# G228X.net
KiCad netlist of a schematic drawn in EAGLE
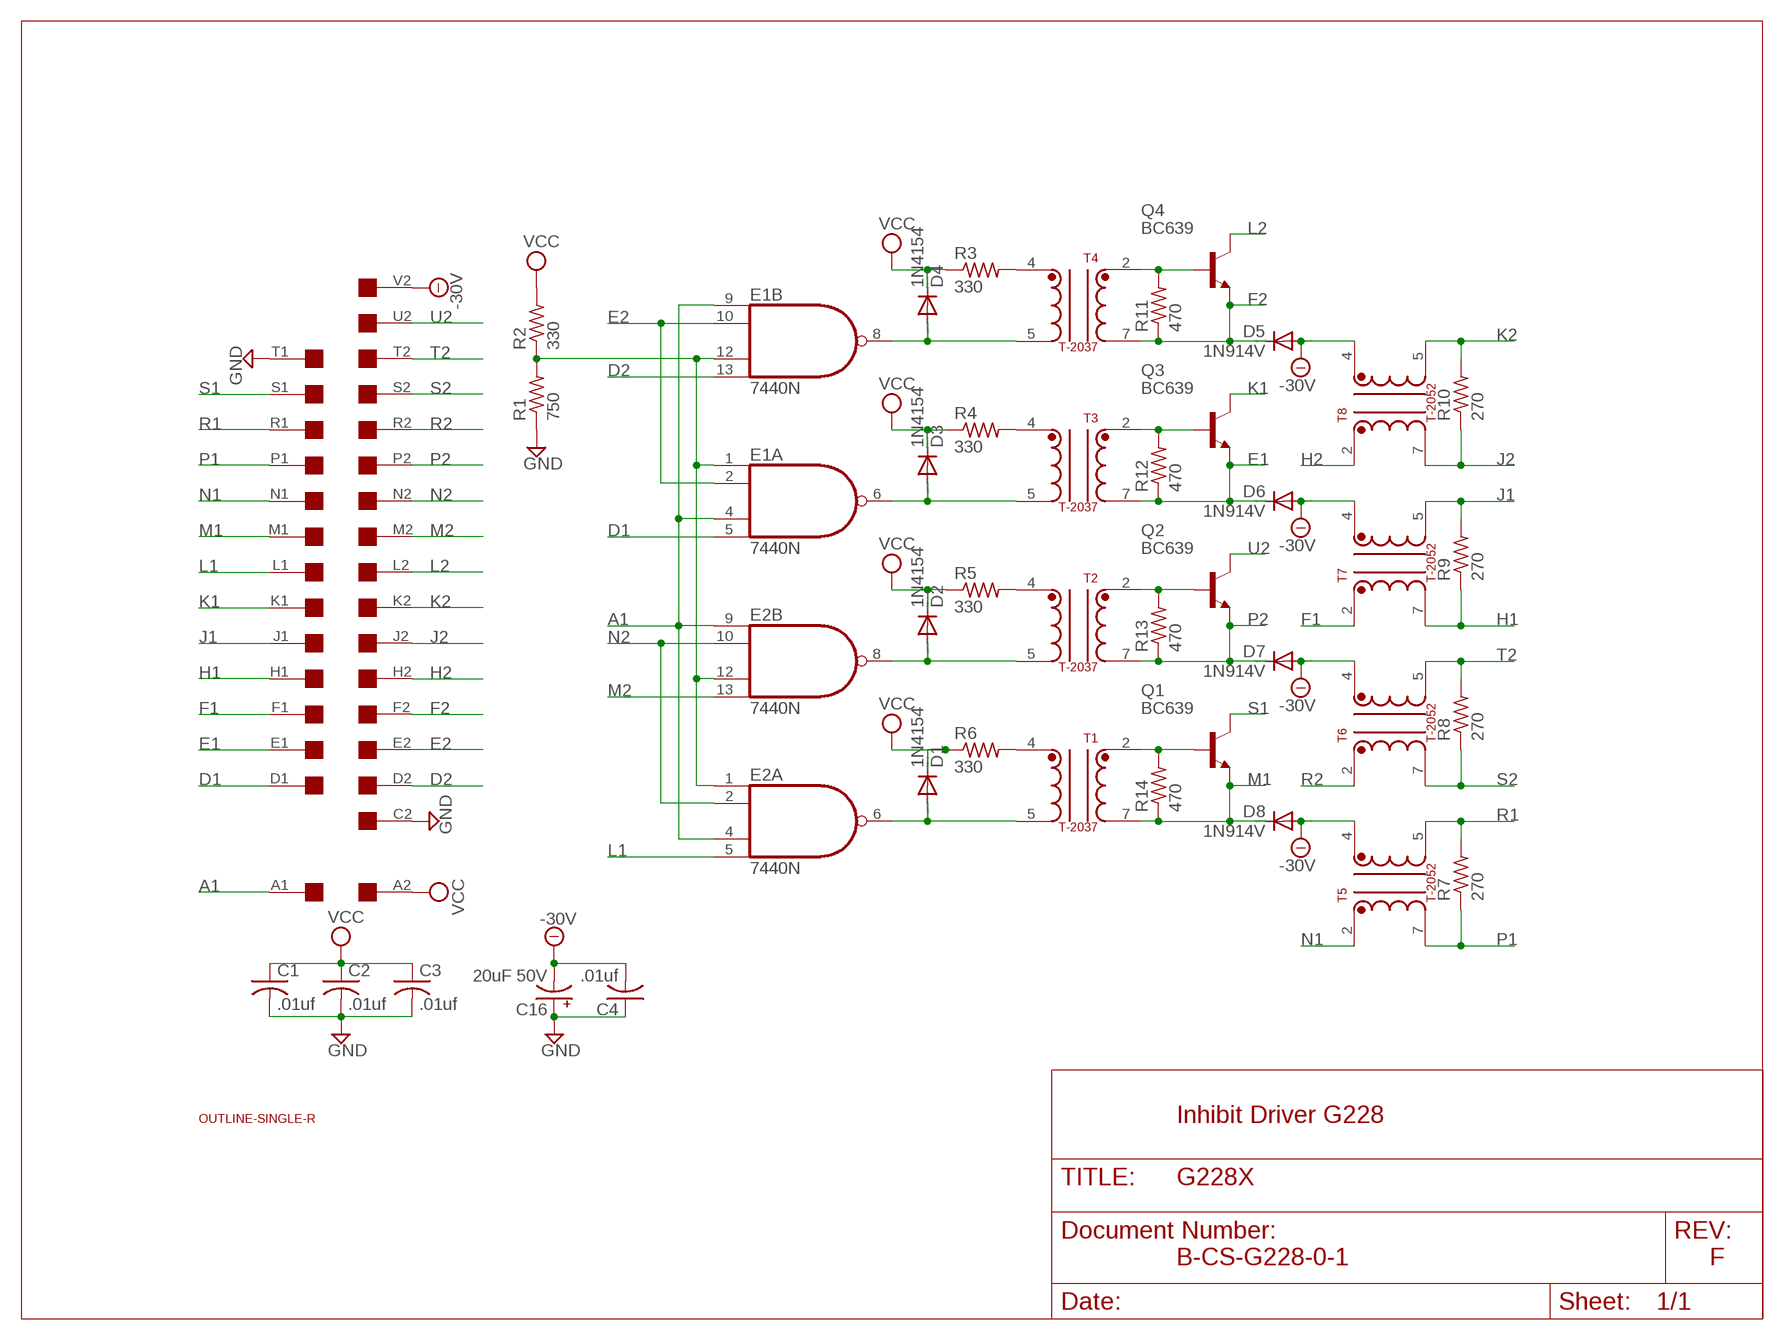
[diagram p0: schematic, sheet 1]

(export (version "E")
  (design (tool "Eeschema 10.0.6"))
  (components
    (comp (ref "C1")
      (value ".01uf")
      (footprint "eagle-import:C050-025X075")
      (libsource (lib "eagle-import") (part "C-US050-025X075"))
    )
    (comp (ref "C2")
      (value ".01uf")
      (footprint "eagle-import:C050-025X075")
      (libsource (lib "eagle-import") (part "C-US050-025X075"))
    )
    (comp (ref "C3")
      (value ".01uf")
      (footprint "eagle-import:C050-025X075")
      (libsource (lib "eagle-import") (part "C-US050-025X075"))
    )
    (comp (ref "C4")
      (value ".01uf")
      (footprint "eagle-import:C050-025X075")
      (libsource (lib "eagle-import") (part "C-US050-025X075"))
    )
    (comp (ref "C16")
      (value "20uF 50V")
      (footprint "eagle-import:E28-8")
      (libsource (lib "eagle-import") (part "CPOL-USE28-8AXIAL"))
    )
    (comp (ref "D1")
      (value "1N4154")
      (footprint "eagle-import:DO35-10")
      (libsource (lib "eagle-import") (part "1N4148DO35-10"))
    )
    (comp (ref "D2")
      (value "1N4154")
      (footprint "eagle-import:DO35-10")
      (libsource (lib "eagle-import") (part "1N4148DO35-10"))
    )
    (comp (ref "D3")
      (value "1N4154")
      (footprint "eagle-import:DO35-10")
      (libsource (lib "eagle-import") (part "1N4148DO35-10"))
    )
    (comp (ref "D4")
      (value "1N4154")
      (footprint "eagle-import:DO35-10")
      (libsource (lib "eagle-import") (part "1N4148DO35-10"))
    )
    (comp (ref "D5")
      (value "1N914V")
      (footprint "eagle-import:DO35-10")
      (libsource (lib "eagle-import") (part "1N4148DO35-10"))
    )
    (comp (ref "D6")
      (value "1N914V")
      (footprint "eagle-import:DO35-10")
      (libsource (lib "eagle-import") (part "1N4148DO35-10"))
    )
    (comp (ref "D7")
      (value "1N914V")
      (footprint "eagle-import:DO35-10")
      (libsource (lib "eagle-import") (part "1N4148DO35-10"))
    )
    (comp (ref "D8")
      (value "1N914V")
      (footprint "eagle-import:DO35-10")
      (libsource (lib "eagle-import") (part "1N4148DO35-10"))
    )
    (comp (ref "E1")
      (value "7440N")
      (footprint "eagle-import:DIL14")
      (libsource (lib "eagle-import") (part "7420NS"))
    )
    (comp (ref "E2")
      (value "7440N")
      (footprint "eagle-import:DIL14")
      (libsource (lib "eagle-import") (part "7420NS"))
    )
    (comp (ref "Q1")
      (value "BC639")
      (footprint "eagle-import:TO39")
      (libsource (lib "eagle-import") (part "-NPN-TO39-EBC2N1613"))
    )
    (comp (ref "Q2")
      (value "BC639")
      (footprint "eagle-import:TO39")
      (libsource (lib "eagle-import") (part "-NPN-TO39-EBC2N1613"))
    )
    (comp (ref "Q3")
      (value "BC639")
      (footprint "eagle-import:TO39")
      (libsource (lib "eagle-import") (part "-NPN-TO39-EBC2N1613"))
    )
    (comp (ref "Q4")
      (value "BC639")
      (footprint "eagle-import:TO39")
      (libsource (lib "eagle-import") (part "-NPN-TO39-EBC2N1613"))
    )
    (comp (ref "R1")
      (value "750")
      (footprint "eagle-import:0207_10")
      (libsource (lib "eagle-import") (part "R-US_0207/10"))
    )
    (comp (ref "R2")
      (value "330")
      (footprint "eagle-import:0207_10")
      (libsource (lib "eagle-import") (part "R-US_0207/10"))
    )
    (comp (ref "R3")
      (value "330")
      (footprint "eagle-import:0207_10")
      (libsource (lib "eagle-import") (part "R-US_0207/10"))
    )
    (comp (ref "R4")
      (value "330")
      (footprint "eagle-import:0207_10")
      (libsource (lib "eagle-import") (part "R-US_0207/10"))
    )
    (comp (ref "R5")
      (value "330")
      (footprint "eagle-import:0207_10")
      (libsource (lib "eagle-import") (part "R-US_0207/10"))
    )
    (comp (ref "R6")
      (value "330")
      (footprint "eagle-import:0207_10")
      (libsource (lib "eagle-import") (part "R-US_0207/10"))
    )
    (comp (ref "R7")
      (value "270")
      (footprint "eagle-import:0207_10")
      (libsource (lib "eagle-import") (part "R-US_0207/10"))
    )
    (comp (ref "R8")
      (value "270")
      (footprint "eagle-import:0207_10")
      (libsource (lib "eagle-import") (part "R-US_0207/10"))
    )
    (comp (ref "R9")
      (value "270")
      (footprint "eagle-import:0207_10")
      (libsource (lib "eagle-import") (part "R-US_0207/10"))
    )
    (comp (ref "R10")
      (value "270")
      (footprint "eagle-import:0207_10")
      (libsource (lib "eagle-import") (part "R-US_0207/10"))
    )
    (comp (ref "R11")
      (value "470")
      (footprint "eagle-import:0207_10")
      (libsource (lib "eagle-import") (part "R-US_0207/10"))
    )
    (comp (ref "R12")
      (value "470")
      (footprint "eagle-import:0207_10")
      (libsource (lib "eagle-import") (part "R-US_0207/10"))
    )
    (comp (ref "R13")
      (value "470")
      (footprint "eagle-import:0207_10")
      (libsource (lib "eagle-import") (part "R-US_0207/10"))
    )
    (comp (ref "R14")
      (value "470")
      (footprint "eagle-import:0207_10")
      (libsource (lib "eagle-import") (part "R-US_0207/10"))
    )
    (comp (ref "T1")
      (value "T-2037")
      (footprint "eagle-import:TRANSFORMER")
      (libsource (lib "eagle-import") (part "T-2037"))
    )
    (comp (ref "T2")
      (value "T-2037")
      (footprint "eagle-import:TRANSFORMER")
      (libsource (lib "eagle-import") (part "T-2037"))
    )
    (comp (ref "T3")
      (value "T-2037")
      (footprint "eagle-import:TRANSFORMER")
      (libsource (lib "eagle-import") (part "T-2037"))
    )
    (comp (ref "T4")
      (value "T-2037")
      (footprint "eagle-import:TRANSFORMER")
      (libsource (lib "eagle-import") (part "T-2037"))
    )
    (comp (ref "T5")
      (value "T-2052")
      (footprint "eagle-import:TRANSFORMER")
      (libsource (lib "eagle-import") (part "T-2052"))
    )
    (comp (ref "T6")
      (value "T-2052")
      (footprint "eagle-import:TRANSFORMER")
      (libsource (lib "eagle-import") (part "T-2052"))
    )
    (comp (ref "T7")
      (value "T-2052")
      (footprint "eagle-import:TRANSFORMER")
      (libsource (lib "eagle-import") (part "T-2052"))
    )
    (comp (ref "T8")
      (value "T-2052")
      (footprint "eagle-import:TRANSFORMER")
      (libsource (lib "eagle-import") (part "T-2052"))
    )
    (comp (ref "U$1")
      (value "SINGLE")
      (footprint "eagle-import:EDGE-CON2")
      (libsource (lib "eagle-import") (part "SINGLE"))
    )
    (comp (ref "U$2")
      (value "OUTLINE-SINGLE-R")
      (footprint "eagle-import:SINGLE-R")
      (libsource (lib "eagle-import") (part "OUTLINE-SINGLE-R"))
    )
  )
  (nets
    (net (code "1") (name "-30V") (class "Default")
      (node (ref "C16") (pin "-") (pinfunction "-_-") (pintype "passive"))
      (node (ref "C4") (pin "2") (pinfunction "2_2") (pintype "passive"))
      (node (ref "D5") (pin "A") (pinfunction "A_A") (pintype "passive"))
      (node (ref "D6") (pin "A") (pinfunction "A_A") (pintype "passive"))
      (node (ref "D7") (pin "A") (pinfunction "A_A") (pintype "passive"))
      (node (ref "D8") (pin "A") (pinfunction "A_A") (pintype "passive"))
      (node (ref "T5") (pin "4") (pinfunction "P$4_4") (pintype "passive"))
      (node (ref "T6") (pin "4") (pinfunction "P$4_4") (pintype "passive"))
      (node (ref "T7") (pin "4") (pinfunction "P$4_4") (pintype "passive"))
      (node (ref "T8") (pin "4") (pinfunction "P$4_4") (pintype "passive"))
      (node (ref "U$1") (pin "V2") (pinfunction "1_V2") (pintype "bidirectional"))
    )
    (net (code "2") (name "/A1") (class "Default")
      (node (ref "E1") (pin "4") (pinfunction "I2_4") (pintype "input"))
      (node (ref "E1") (pin "9") (pinfunction "I0_9") (pintype "input"))
      (node (ref "E2") (pin "4") (pinfunction "I2_4") (pintype "input"))
      (node (ref "E2") (pin "9") (pinfunction "I0_9") (pintype "input"))
      (node (ref "U$1") (pin "A1") (pinfunction "1_A1") (pintype "bidirectional"))
    )
    (net (code "3") (name "/D1") (class "Default")
      (node (ref "E1") (pin "5") (pinfunction "I3_5") (pintype "input"))
      (node (ref "U$1") (pin "D1") (pinfunction "1_D1") (pintype "bidirectional"))
    )
    (net (code "4") (name "/D2") (class "Default")
      (node (ref "E1") (pin "13") (pinfunction "I3_13") (pintype "input"))
      (node (ref "U$1") (pin "D2") (pinfunction "1_D2") (pintype "bidirectional"))
    )
    (net (code "5") (name "/E1") (class "Default")
      (node (ref "D6") (pin "C") (pinfunction "C_C") (pintype "passive"))
      (node (ref "Q3") (pin "1") (pinfunction "E_1") (pintype "passive"))
      (node (ref "R12") (pin "1") (pinfunction "1_1") (pintype "passive"))
      (node (ref "T3") (pin "7") (pinfunction "P$7_7") (pintype "passive"))
      (node (ref "U$1") (pin "E1") (pinfunction "1_E1") (pintype "bidirectional"))
    )
    (net (code "6") (name "/E2") (class "Default")
      (node (ref "E1") (pin "10") (pinfunction "I1_10") (pintype "input"))
      (node (ref "E1") (pin "2") (pinfunction "I1_2") (pintype "input"))
      (node (ref "U$1") (pin "E2") (pinfunction "1_E2") (pintype "bidirectional"))
    )
    (net (code "7") (name "/F1") (class "Default")
      (node (ref "T7") (pin "2") (pinfunction "P$2_2") (pintype "passive"))
      (node (ref "U$1") (pin "F1") (pinfunction "1_F1") (pintype "bidirectional"))
    )
    (net (code "8") (name "/F2") (class "Default")
      (node (ref "D5") (pin "C") (pinfunction "C_C") (pintype "passive"))
      (node (ref "Q4") (pin "1") (pinfunction "E_1") (pintype "passive"))
      (node (ref "R11") (pin "1") (pinfunction "1_1") (pintype "passive"))
      (node (ref "T4") (pin "7") (pinfunction "P$7_7") (pintype "passive"))
      (node (ref "U$1") (pin "F2") (pinfunction "1_F2") (pintype "bidirectional"))
    )
    (net (code "9") (name "/H1") (class "Default")
      (node (ref "R9") (pin "1") (pinfunction "1_1") (pintype "passive"))
      (node (ref "T7") (pin "7") (pinfunction "P$7_7") (pintype "passive"))
      (node (ref "U$1") (pin "H1") (pinfunction "1_H1") (pintype "bidirectional"))
    )
    (net (code "10") (name "/H2") (class "Default")
      (node (ref "T8") (pin "2") (pinfunction "P$2_2") (pintype "passive"))
      (node (ref "U$1") (pin "H2") (pinfunction "1_H2") (pintype "bidirectional"))
    )
    (net (code "11") (name "/J1") (class "Default")
      (node (ref "R9") (pin "2") (pinfunction "2_2") (pintype "passive"))
      (node (ref "T7") (pin "5") (pinfunction "P$5_5") (pintype "passive"))
      (node (ref "U$1") (pin "J1") (pinfunction "1_J1") (pintype "bidirectional"))
    )
    (net (code "12") (name "/J2") (class "Default")
      (node (ref "R10") (pin "1") (pinfunction "1_1") (pintype "passive"))
      (node (ref "T8") (pin "7") (pinfunction "P$7_7") (pintype "passive"))
      (node (ref "U$1") (pin "J2") (pinfunction "1_J2") (pintype "bidirectional"))
    )
    (net (code "13") (name "/K1") (class "Default")
      (node (ref "Q3") (pin "3") (pinfunction "C_3") (pintype "passive"))
      (node (ref "U$1") (pin "K1") (pinfunction "1_K1") (pintype "bidirectional"))
    )
    (net (code "14") (name "/K2") (class "Default")
      (node (ref "R10") (pin "2") (pinfunction "2_2") (pintype "passive"))
      (node (ref "T8") (pin "5") (pinfunction "P$5_5") (pintype "passive"))
      (node (ref "U$1") (pin "K2") (pinfunction "1_K2") (pintype "bidirectional"))
    )
    (net (code "15") (name "/L1") (class "Default")
      (node (ref "E2") (pin "5") (pinfunction "I3_5") (pintype "input"))
      (node (ref "U$1") (pin "L1") (pinfunction "1_L1") (pintype "bidirectional"))
    )
    (net (code "16") (name "/L2") (class "Default")
      (node (ref "Q4") (pin "3") (pinfunction "C_3") (pintype "passive"))
      (node (ref "U$1") (pin "L2") (pinfunction "1_L2") (pintype "bidirectional"))
    )
    (net (code "17") (name "/M1") (class "Default")
      (node (ref "D8") (pin "C") (pinfunction "C_C") (pintype "passive"))
      (node (ref "Q1") (pin "1") (pinfunction "E_1") (pintype "passive"))
      (node (ref "R14") (pin "1") (pinfunction "1_1") (pintype "passive"))
      (node (ref "T1") (pin "7") (pinfunction "P$7_7") (pintype "passive"))
      (node (ref "U$1") (pin "M1") (pinfunction "1_M1") (pintype "bidirectional"))
    )
    (net (code "18") (name "/M2") (class "Default")
      (node (ref "E2") (pin "13") (pinfunction "I3_13") (pintype "input"))
      (node (ref "U$1") (pin "M2") (pinfunction "1_M2") (pintype "bidirectional"))
    )
    (net (code "19") (name "/N1") (class "Default")
      (node (ref "T5") (pin "2") (pinfunction "P$2_2") (pintype "passive"))
      (node (ref "U$1") (pin "N1") (pinfunction "1_N1") (pintype "bidirectional"))
    )
    (net (code "20") (name "/N2") (class "Default")
      (node (ref "E2") (pin "10") (pinfunction "I1_10") (pintype "input"))
      (node (ref "E2") (pin "2") (pinfunction "I1_2") (pintype "input"))
      (node (ref "U$1") (pin "N2") (pinfunction "1_N2") (pintype "bidirectional"))
    )
    (net (code "21") (name "/P1") (class "Default")
      (node (ref "R7") (pin "1") (pinfunction "1_1") (pintype "passive"))
      (node (ref "T5") (pin "7") (pinfunction "P$7_7") (pintype "passive"))
      (node (ref "U$1") (pin "P1") (pinfunction "1_P1") (pintype "bidirectional"))
    )
    (net (code "22") (name "/P2") (class "Default")
      (node (ref "D7") (pin "C") (pinfunction "C_C") (pintype "passive"))
      (node (ref "Q2") (pin "1") (pinfunction "E_1") (pintype "passive"))
      (node (ref "R13") (pin "1") (pinfunction "1_1") (pintype "passive"))
      (node (ref "T2") (pin "7") (pinfunction "P$7_7") (pintype "passive"))
      (node (ref "U$1") (pin "P2") (pinfunction "1_P2") (pintype "bidirectional"))
    )
    (net (code "23") (name "/R1") (class "Default")
      (node (ref "R7") (pin "2") (pinfunction "2_2") (pintype "passive"))
      (node (ref "T5") (pin "5") (pinfunction "P$5_5") (pintype "passive"))
      (node (ref "U$1") (pin "R1") (pinfunction "1_R1") (pintype "bidirectional"))
    )
    (net (code "24") (name "/R2") (class "Default")
      (node (ref "T6") (pin "2") (pinfunction "P$2_2") (pintype "passive"))
      (node (ref "U$1") (pin "R2") (pinfunction "1_R2") (pintype "bidirectional"))
    )
    (net (code "25") (name "/S1") (class "Default")
      (node (ref "Q1") (pin "3") (pinfunction "C_3") (pintype "passive"))
      (node (ref "U$1") (pin "S1") (pinfunction "1_S1") (pintype "bidirectional"))
    )
    (net (code "26") (name "/S2") (class "Default")
      (node (ref "R8") (pin "1") (pinfunction "1_1") (pintype "passive"))
      (node (ref "T6") (pin "7") (pinfunction "P$7_7") (pintype "passive"))
      (node (ref "U$1") (pin "S2") (pinfunction "1_S2") (pintype "bidirectional"))
    )
    (net (code "27") (name "/T2") (class "Default")
      (node (ref "R8") (pin "2") (pinfunction "2_2") (pintype "passive"))
      (node (ref "T6") (pin "5") (pinfunction "P$5_5") (pintype "passive"))
      (node (ref "U$1") (pin "T2") (pinfunction "1_T2") (pintype "bidirectional"))
    )
    (net (code "28") (name "/U2") (class "Default")
      (node (ref "Q2") (pin "3") (pinfunction "C_3") (pintype "passive"))
      (node (ref "U$1") (pin "U2") (pinfunction "1_U2") (pintype "bidirectional"))
    )
    (net (code "29") (name "GND") (class "Default")
      (node (ref "C1") (pin "2") (pinfunction "2_2") (pintype "passive"))
      (node (ref "C16") (pin "+") (pinfunction "+_+") (pintype "passive"))
      (node (ref "C2") (pin "2") (pinfunction "2_2") (pintype "passive"))
      (node (ref "C3") (pin "2") (pinfunction "2_2") (pintype "passive"))
      (node (ref "C4") (pin "1") (pinfunction "1_1") (pintype "passive"))
      (node (ref "R1") (pin "1") (pinfunction "1_1") (pintype "passive"))
      (node (ref "U$1") (pin "C2") (pinfunction "1_C2") (pintype "bidirectional"))
      (node (ref "U$1") (pin "T1") (pinfunction "1_T1") (pintype "bidirectional"))
    )
    (net (code "30") (name "Net-(E1A-I0)") (class "Default")
      (node (ref "E1") (pin "1") (pinfunction "I0_1") (pintype "input"))
      (node (ref "E1") (pin "12") (pinfunction "I2_12") (pintype "input"))
      (node (ref "E2") (pin "1") (pinfunction "I0_1") (pintype "input"))
      (node (ref "E2") (pin "12") (pinfunction "I2_12") (pintype "input"))
      (node (ref "R1") (pin "2") (pinfunction "2_2") (pintype "passive"))
      (node (ref "R2") (pin "1") (pinfunction "1_1") (pintype "passive"))
    )
    (net (code "31") (name "Net-(E1A-O)") (class "Default")
      (node (ref "D3") (pin "A") (pinfunction "A_A") (pintype "passive"))
      (node (ref "E1") (pin "6") (pinfunction "O_6") (pintype "output"))
      (node (ref "T3") (pin "5") (pinfunction "P$5_5") (pintype "passive"))
    )
    (net (code "32") (name "Net-(E1B-O)") (class "Default")
      (node (ref "D4") (pin "A") (pinfunction "A_A") (pintype "passive"))
      (node (ref "E1") (pin "8") (pinfunction "O_8") (pintype "output"))
      (node (ref "T4") (pin "5") (pinfunction "P$5_5") (pintype "passive"))
    )
    (net (code "33") (name "Net-(E2A-O)") (class "Default")
      (node (ref "D1") (pin "A") (pinfunction "A_A") (pintype "passive"))
      (node (ref "E2") (pin "6") (pinfunction "O_6") (pintype "output"))
      (node (ref "T1") (pin "5") (pinfunction "P$5_5") (pintype "passive"))
    )
    (net (code "34") (name "Net-(E2B-O)") (class "Default")
      (node (ref "D2") (pin "A") (pinfunction "A_A") (pintype "passive"))
      (node (ref "E2") (pin "8") (pinfunction "O_8") (pintype "output"))
      (node (ref "T2") (pin "5") (pinfunction "P$5_5") (pintype "passive"))
    )
    (net (code "35") (name "Net-(Q1-B)") (class "Default")
      (node (ref "Q1") (pin "2") (pinfunction "B_2") (pintype "passive"))
      (node (ref "R14") (pin "2") (pinfunction "2_2") (pintype "passive"))
      (node (ref "T1") (pin "2") (pinfunction "P$2_2") (pintype "passive"))
    )
    (net (code "36") (name "Net-(Q2-B)") (class "Default")
      (node (ref "Q2") (pin "2") (pinfunction "B_2") (pintype "passive"))
      (node (ref "R13") (pin "2") (pinfunction "2_2") (pintype "passive"))
      (node (ref "T2") (pin "2") (pinfunction "P$2_2") (pintype "passive"))
    )
    (net (code "37") (name "Net-(Q3-B)") (class "Default")
      (node (ref "Q3") (pin "2") (pinfunction "B_2") (pintype "passive"))
      (node (ref "R12") (pin "2") (pinfunction "2_2") (pintype "passive"))
      (node (ref "T3") (pin "2") (pinfunction "P$2_2") (pintype "passive"))
    )
    (net (code "38") (name "Net-(Q4-B)") (class "Default")
      (node (ref "Q4") (pin "2") (pinfunction "B_2") (pintype "passive"))
      (node (ref "R11") (pin "2") (pinfunction "2_2") (pintype "passive"))
      (node (ref "T4") (pin "2") (pinfunction "P$2_2") (pintype "passive"))
    )
    (net (code "39") (name "Net-(T1-P$4)") (class "Default")
      (node (ref "R6") (pin "2") (pinfunction "2_2") (pintype "passive"))
      (node (ref "T1") (pin "4") (pinfunction "P$4_4") (pintype "passive"))
    )
    (net (code "40") (name "Net-(T2-P$4)") (class "Default")
      (node (ref "R5") (pin "2") (pinfunction "2_2") (pintype "passive"))
      (node (ref "T2") (pin "4") (pinfunction "P$4_4") (pintype "passive"))
    )
    (net (code "41") (name "Net-(T3-P$4)") (class "Default")
      (node (ref "R4") (pin "2") (pinfunction "2_2") (pintype "passive"))
      (node (ref "T3") (pin "4") (pinfunction "P$4_4") (pintype "passive"))
    )
    (net (code "42") (name "Net-(T4-P$4)") (class "Default")
      (node (ref "R3") (pin "2") (pinfunction "2_2") (pintype "passive"))
      (node (ref "T4") (pin "4") (pinfunction "P$4_4") (pintype "passive"))
    )
    (net (code "43") (name "VCC") (class "Default")
      (node (ref "C1") (pin "1") (pinfunction "1_1") (pintype "passive"))
      (node (ref "C2") (pin "1") (pinfunction "1_1") (pintype "passive"))
      (node (ref "C3") (pin "1") (pinfunction "1_1") (pintype "passive"))
      (node (ref "D1") (pin "C") (pinfunction "C_C") (pintype "passive"))
      (node (ref "D2") (pin "C") (pinfunction "C_C") (pintype "passive"))
      (node (ref "D3") (pin "C") (pinfunction "C_C") (pintype "passive"))
      (node (ref "D4") (pin "C") (pinfunction "C_C") (pintype "passive"))
      (node (ref "R2") (pin "2") (pinfunction "2_2") (pintype "passive"))
      (node (ref "R3") (pin "1") (pinfunction "1_1") (pintype "passive"))
      (node (ref "R4") (pin "1") (pinfunction "1_1") (pintype "passive"))
      (node (ref "R5") (pin "1") (pinfunction "1_1") (pintype "passive"))
      (node (ref "R6") (pin "1") (pinfunction "1_1") (pintype "passive"))
      (node (ref "U$1") (pin "A2") (pinfunction "1_A2") (pintype "bidirectional"))
    )
  )
)
